# PWR-Switch.net
KiCad netlist of a schematic drawn in Altium Designer
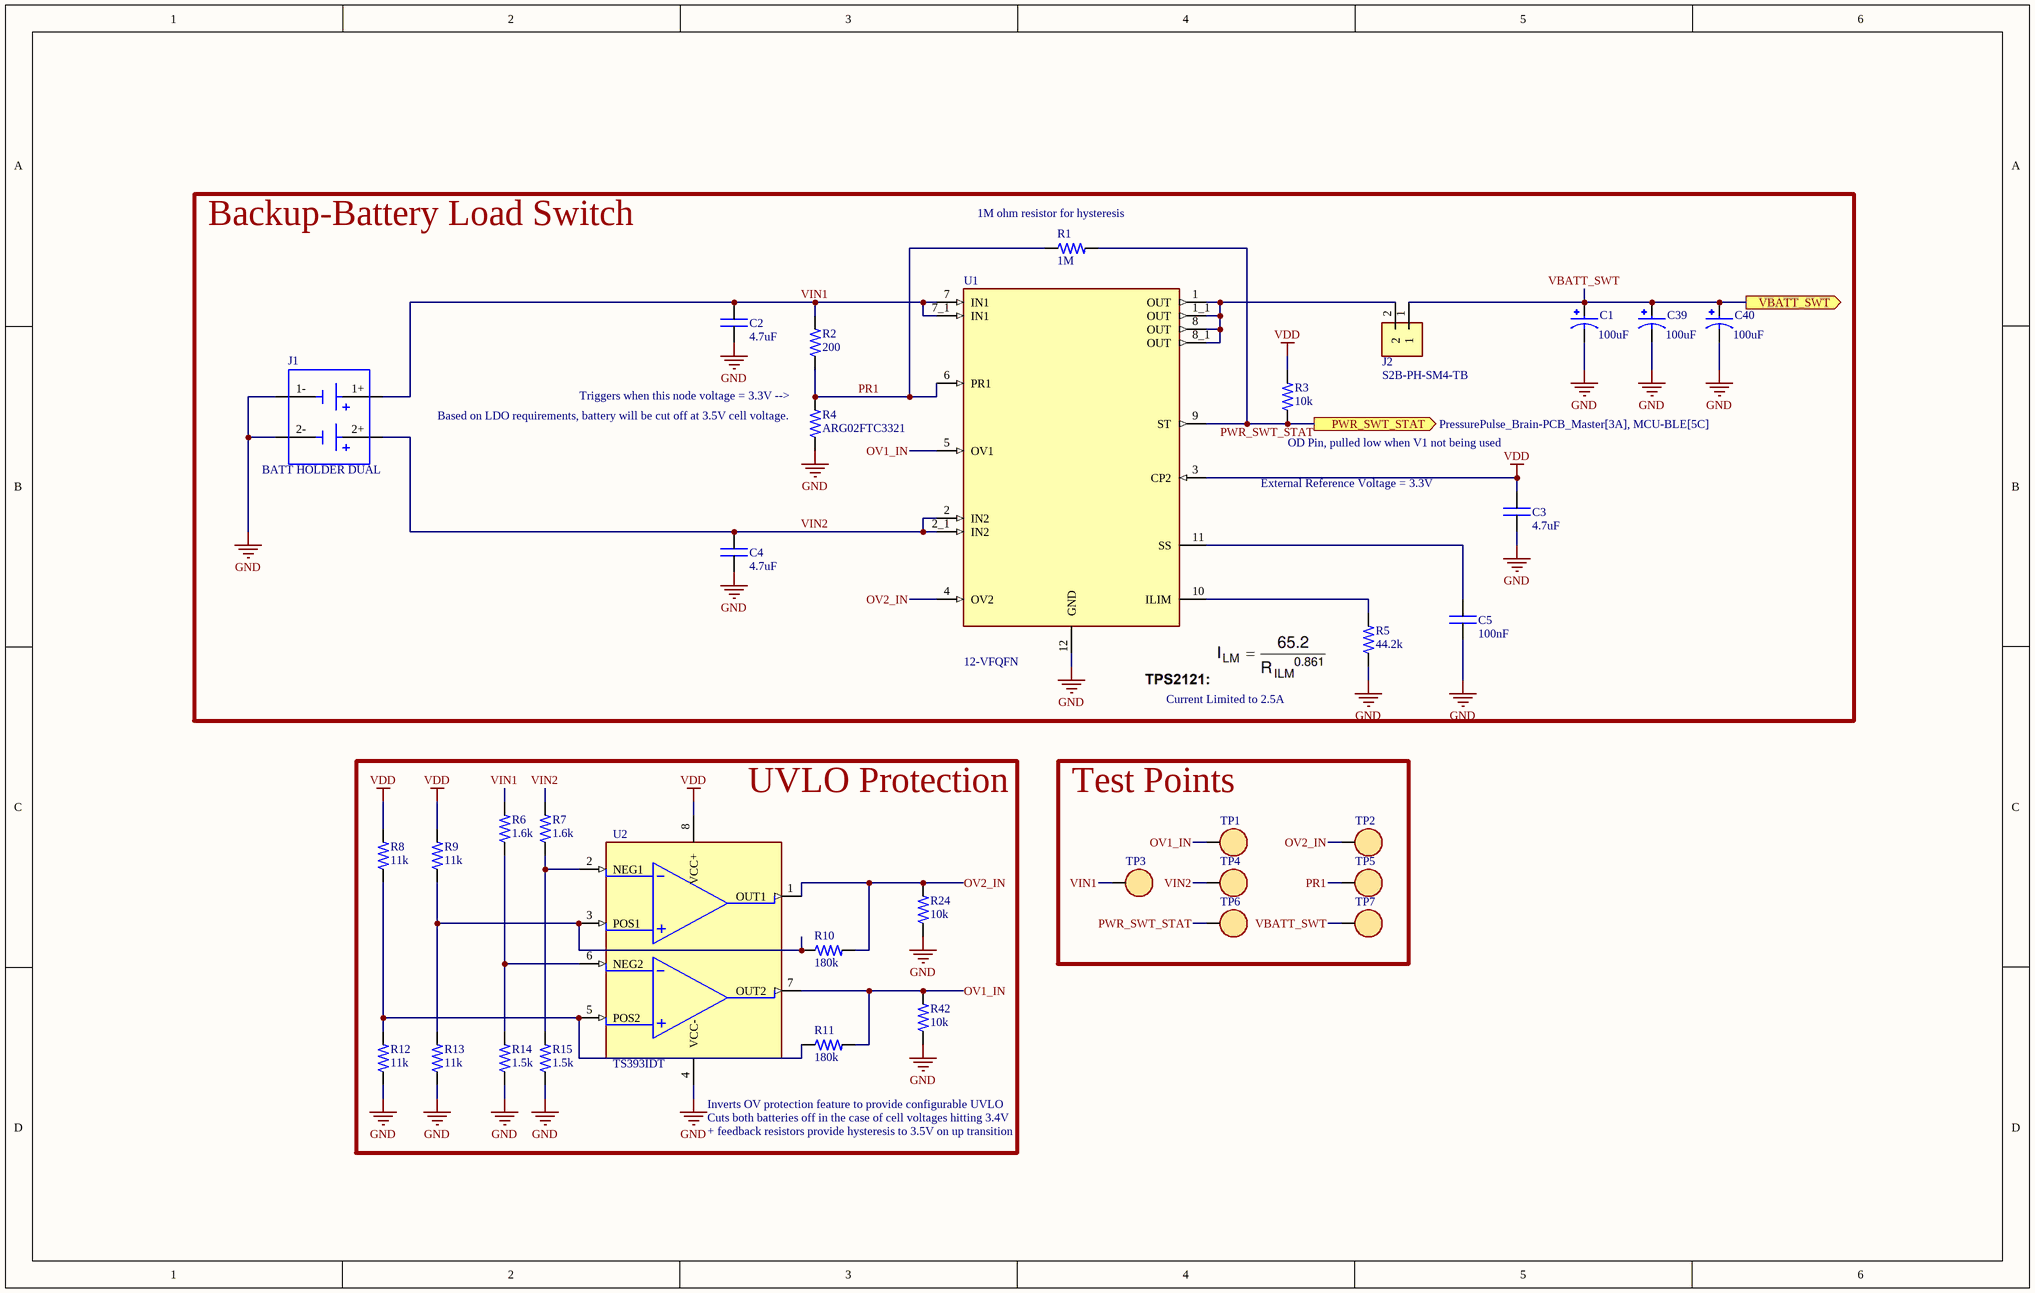
[diagram p0: PWR-Switch.SchDoc]

(export (version "E")
  (design (tool "Eeschema 10.0.6"))
  (components
    (comp (ref "C1")
      (value "100uF")
      (footprint "PressurePulse:CAP_POL_SMD")
      (fields (field (name "MFR") "PANASONIC") (field (name "Comment") "CAP POLARIZED"))
      (libsource (lib "PressurePulse") (part "CAP POLARIZED"))
    )
    (comp (ref "C2")
      (value "4.7uF")
      (footprint "PressurePulse:0402C")
      (description "Capacitor")
      (fields (field (name "Comment") "CAP"))
      (libsource (lib "PressurePulse") (part "CAP"))
    )
    (comp (ref "C3")
      (value "4.7uF")
      (footprint "PressurePulse:0402C")
      (description "Capacitor")
      (fields (field (name "Comment") "CAP"))
      (libsource (lib "PressurePulse") (part "CAP"))
    )
    (comp (ref "C4")
      (value "4.7uF")
      (footprint "PressurePulse:0402C")
      (description "Capacitor")
      (fields (field (name "Comment") "CAP"))
      (libsource (lib "PressurePulse") (part "CAP"))
    )
    (comp (ref "C5")
      (value "100nF")
      (footprint "PressurePulse:0402C")
      (description "Capaicitor")
      (fields (field (name "Comment") "CAP"))
      (libsource (lib "PressurePulse") (part "CAP"))
    )
    (comp (ref "C39")
      (value "100uF")
      (footprint "PressurePulse:CAP_POL_SMD")
      (fields (field (name "MFR") "PANASONIC") (field (name "Comment") "CAP POLARIZED"))
      (libsource (lib "PressurePulse") (part "CAP POLARIZED"))
    )
    (comp (ref "C40")
      (value "100uF")
      (footprint "PressurePulse:CAP_POL_SMD")
      (fields (field (name "MFR") "PANASONIC") (field (name "Comment") "CAP POLARIZED"))
      (libsource (lib "PressurePulse") (part "CAP POLARIZED"))
    )
    (comp (ref "J1")
      (value "BATT HOLDER DUAL")
      (footprint "PressurePulse:18650_DUAL_PARALLEL")
      (description "Battery Holder (Open) 18650 2 Cell PC Pin")
      (fields (field (name "MFR") "MPD (Memory Protection Devices)"))
      (libsource (lib "PressurePulse") (part "BATT HOLDER DUAL"))
    )
    (comp (ref "J2")
      (value "S2B-PH-SM4-TB")
      (footprint "PressurePulse:JST_PH-2POS-SMT-RA")
      (description "Connector Header Surface Mount, Right Angle 2 position 0.079 (2.00mm)")
      (fields (field (name "MFR") "JST Sales"))
      (libsource (lib "PressurePulse") (part "JST CONN 2POS PH"))
    )
    (comp (ref "R1")
      (value "1M")
      (footprint "PressurePulse:0402R")
      (description "Resistor")
      (fields (field (name "Comment") "RES"))
      (libsource (lib "PressurePulse") (part "RES"))
    )
    (comp (ref "R2")
      (value "200")
      (footprint "PressurePulse:0402R")
      (description "Resistor")
      (fields (field (name "TOLERANCE") "0.5%") (field (name "Comment") "RES"))
      (libsource (lib "PressurePulse") (part "RES"))
    )
    (comp (ref "R3")
      (value "10k")
      (footprint "PressurePulse:0402R")
      (description "Resistor")
      (fields (field (name "Comment") "RES"))
      (libsource (lib "PressurePulse") (part "RES"))
    )
    (comp (ref "R4")
      (value "ARG02FTC3321")
      (footprint "PressurePulse:0402R")
      (description "Resistor")
      (fields (field (name "TOLERANCE") "1%") (field (name "Comment") "RES"))
      (libsource (lib "PressurePulse") (part "RES"))
    )
    (comp (ref "R5")
      (value "44.2k")
      (footprint "PressurePulse:0402R")
      (description "Resistor")
      (fields (field (name "TOLERANCE") "1%") (field (name "Comment") "RES"))
      (libsource (lib "PressurePulse") (part "RES"))
    )
    (comp (ref "R6")
      (value "1.6k")
      (footprint "PressurePulse:0603-RES")
      (description "Resistor")
      (fields (field (name "TOLERANCE") "0.5%") (field (name "Comment") "RES"))
      (libsource (lib "PressurePulse") (part "RES"))
    )
    (comp (ref "R7")
      (value "1.6k")
      (footprint "PressurePulse:0603-RES")
      (description "Resistor")
      (fields (field (name "TOLERANCE") "0.5%") (field (name "Comment") "RES"))
      (libsource (lib "PressurePulse") (part "RES"))
    )
    (comp (ref "R8")
      (value "11k")
      (footprint "PressurePulse:0402R")
      (description "Resistor")
      (fields (field (name "TOLERANCE") "0.5%") (field (name "Comment") "RES"))
      (libsource (lib "PressurePulse") (part "RES"))
    )
    (comp (ref "R9")
      (value "11k")
      (footprint "PressurePulse:0402R")
      (description "Resistor")
      (fields (field (name "TOLERANCE") "0.5%") (field (name "Comment") "RES"))
      (libsource (lib "PressurePulse") (part "RES"))
    )
    (comp (ref "R10")
      (value "180k")
      (footprint "PressurePulse:0402R")
      (description "Resistor")
      (fields (field (name "Comment") "RES"))
      (libsource (lib "PressurePulse") (part "RES"))
    )
    (comp (ref "R11")
      (value "180k")
      (footprint "PressurePulse:0402R")
      (description "Resistor")
      (fields (field (name "Comment") "RES"))
      (libsource (lib "PressurePulse") (part "RES"))
    )
    (comp (ref "R12")
      (value "11k")
      (footprint "PressurePulse:0402R")
      (description "Resistor")
      (fields (field (name "TOLERANCE") "0.5%") (field (name "Comment") "RES"))
      (libsource (lib "PressurePulse") (part "RES"))
    )
    (comp (ref "R13")
      (value "11k")
      (footprint "PressurePulse:0402R")
      (description "Resistor")
      (fields (field (name "TOLERANCE") "0.5%") (field (name "Comment") "RES"))
      (libsource (lib "PressurePulse") (part "RES"))
    )
    (comp (ref "R14")
      (value "1.5k")
      (footprint "PressurePulse:0603-RES")
      (description "Resistor")
      (fields (field (name "TOLERANCE") "0.5%") (field (name "Comment") "RES"))
      (libsource (lib "PressurePulse") (part "RES"))
    )
    (comp (ref "R15")
      (value "1.5k")
      (footprint "PressurePulse:0603-RES")
      (description "Resistor")
      (fields (field (name "TOLERANCE") "0.5%") (field (name "Comment") "RES"))
      (libsource (lib "PressurePulse") (part "RES"))
    )
    (comp (ref "R24")
      (value "10k")
      (footprint "PressurePulse:0402R")
      (description "Resistor")
      (fields (field (name "Comment") "RES"))
      (libsource (lib "PressurePulse") (part "RES"))
    )
    (comp (ref "R42")
      (value "10k")
      (footprint "PressurePulse:0402R")
      (description "Resistor")
      (fields (field (name "Comment") "RES"))
      (libsource (lib "PressurePulse") (part "RES"))
    )
    (comp (ref "TP1")
      (value "RH-5019")
      (footprint "PressurePulse:TP - RH-5019")
      (fields (field (name "MFR") "ronghe"))
      (libsource (lib "PressurePulse") (part "TEST POINT"))
    )
    (comp (ref "TP2")
      (value "RH-5019")
      (footprint "PressurePulse:TP - RH-5019")
      (fields (field (name "MFR") "ronghe"))
      (libsource (lib "PressurePulse") (part "TEST POINT"))
    )
    (comp (ref "TP3")
      (value "RH-5019")
      (footprint "PressurePulse:TP - RH-5019")
      (fields (field (name "MFR") "ronghe"))
      (libsource (lib "PressurePulse") (part "TEST POINT"))
    )
    (comp (ref "TP4")
      (value "RH-5019")
      (footprint "PressurePulse:TP - RH-5019")
      (fields (field (name "MFR") "ronghe"))
      (libsource (lib "PressurePulse") (part "TEST POINT"))
    )
    (comp (ref "TP5")
      (value "RH-5019")
      (footprint "PressurePulse:TP - RH-5019")
      (fields (field (name "MFR") "ronghe"))
      (libsource (lib "PressurePulse") (part "TEST POINT"))
    )
    (comp (ref "TP6")
      (value "RH-5019")
      (footprint "PressurePulse:TP - RH-5019")
      (fields (field (name "MFR") "ronghe"))
      (libsource (lib "PressurePulse") (part "TEST POINT"))
    )
    (comp (ref "TP7")
      (value "RH-5019")
      (footprint "PressurePulse:TP - RH-5019")
      (fields (field (name "MFR") "ronghe"))
      (libsource (lib "PressurePulse") (part "TEST POINT"))
    )
    (comp (ref "U1")
      (value "12-VFQFN")
      (footprint "PressurePulse:12-VFQFN")
      (description "2.7-V to 22-V, 56-ma, 4.5-A, power mux with seamless switchover")
      (fields (field (name "MFR") "Texas Instruments"))
      (libsource (lib "PressurePulse") (part "TPS2121RUXR"))
    )
    (comp (ref "U2")
      (value "TS393IDT")
      (footprint "PressurePulse:SOIC-8")
      (description "Micropower dual CMOS voltage comparators")
      (fields (field (name "MFR") "STMicroelectronics"))
      (libsource (lib "PressurePulse") (part "DUAL COMPARATOR"))
    )
  )
  (nets
    (net (code "1") (name "/OV1_IN") (class "Default")
      (node (ref "R11") (pin "2") (pinfunction "2_2") (pintype "passive"))
      (node (ref "R42") (pin "2") (pinfunction "2_2") (pintype "passive"))
      (node (ref "TP1") (pin "1") (pinfunction "1_1") (pintype "passive"))
      (node (ref "U1") (pin "5") (pinfunction "OV1_5") (pintype "input"))
      (node (ref "U2") (pin "7") (pinfunction "OUT2_7") (pintype "output"))
    )
    (net (code "2") (name "/OV2_IN") (class "Default")
      (node (ref "R10") (pin "2") (pinfunction "2_2") (pintype "passive"))
      (node (ref "R24") (pin "2") (pinfunction "2_2") (pintype "passive"))
      (node (ref "TP2") (pin "1") (pinfunction "1_1") (pintype "passive"))
      (node (ref "U1") (pin "4") (pinfunction "OV2_4") (pintype "input"))
      (node (ref "U2") (pin "1") (pinfunction "OUT1_1") (pintype "output"))
    )
    (net (code "3") (name "/PR1") (class "Default")
      (node (ref "R1") (pin "1") (pinfunction "1_1") (pintype "passive"))
      (node (ref "R2") (pin "1") (pinfunction "1_1") (pintype "passive"))
      (node (ref "R4") (pin "2") (pinfunction "2_2") (pintype "passive"))
      (node (ref "TP5") (pin "1") (pinfunction "1_1") (pintype "passive"))
      (node (ref "U1") (pin "6") (pinfunction "PR1_6") (pintype "input"))
    )
    (net (code "4") (name "/PWR_SWT_STAT") (class "Default")
      (node (ref "R1") (pin "2") (pinfunction "2_2") (pintype "passive"))
      (node (ref "R3") (pin "1") (pinfunction "1_1") (pintype "passive"))
      (node (ref "TP6") (pin "1") (pinfunction "1_1") (pintype "passive"))
      (node (ref "U1") (pin "9") (pinfunction "ST_9") (pintype "output"))
    )
    (net (code "5") (name "/VBATT_SWT") (class "Default")
      (node (ref "C1") (pin "1") (pinfunction "1_1") (pintype "passive"))
      (node (ref "C39") (pin "1") (pinfunction "1_1") (pintype "passive"))
      (node (ref "C40") (pin "1") (pinfunction "1_1") (pintype "passive"))
      (node (ref "J2") (pin "1") (pinfunction "1_1") (pintype "passive"))
      (node (ref "TP7") (pin "1") (pinfunction "1_1") (pintype "passive"))
    )
    (net (code "6") (name "/VIN1") (class "Default")
      (node (ref "C2") (pin "2") (pinfunction "2_2") (pintype "passive"))
      (node (ref "J1") (pin "1+") (pinfunction "1+_1+") (pintype "passive"))
      (node (ref "R2") (pin "2") (pinfunction "2_2") (pintype "passive"))
      (node (ref "R6") (pin "2") (pinfunction "2_2") (pintype "passive"))
      (node (ref "TP3") (pin "1") (pinfunction "1_1") (pintype "passive"))
      (node (ref "U1") (pin "7") (pinfunction "IN1_7") (pintype "input"))
      (node (ref "U1") (pin "7_1") (pinfunction "IN1_7_1") (pintype "input"))
    )
    (net (code "7") (name "/VIN2") (class "Default")
      (node (ref "C4") (pin "2") (pinfunction "2_2") (pintype "passive"))
      (node (ref "J1") (pin "2+") (pinfunction "2+_2+") (pintype "passive"))
      (node (ref "R7") (pin "2") (pinfunction "2_2") (pintype "passive"))
      (node (ref "TP4") (pin "1") (pinfunction "1_1") (pintype "passive"))
      (node (ref "U1") (pin "2") (pinfunction "IN2_2") (pintype "input"))
      (node (ref "U1") (pin "2_1") (pinfunction "IN2_2_1") (pintype "input"))
    )
    (net (code "8") (name "GND") (class "Default")
      (node (ref "C1") (pin "2") (pinfunction "2_2") (pintype "passive"))
      (node (ref "C2") (pin "1") (pinfunction "1_1") (pintype "passive"))
      (node (ref "C3") (pin "1") (pinfunction "1_1") (pintype "passive"))
      (node (ref "C39") (pin "2") (pinfunction "2_2") (pintype "passive"))
      (node (ref "C4") (pin "1") (pinfunction "1_1") (pintype "passive"))
      (node (ref "C40") (pin "2") (pinfunction "2_2") (pintype "passive"))
      (node (ref "C5") (pin "1") (pinfunction "1_1") (pintype "passive"))
      (node (ref "J1") (pin "1-") (pinfunction "1-_1-") (pintype "passive"))
      (node (ref "J1") (pin "2-") (pinfunction "2-_2-") (pintype "passive"))
      (node (ref "R12") (pin "1") (pinfunction "1_1") (pintype "passive"))
      (node (ref "R13") (pin "1") (pinfunction "1_1") (pintype "passive"))
      (node (ref "R14") (pin "1") (pinfunction "1_1") (pintype "passive"))
      (node (ref "R15") (pin "1") (pinfunction "1_1") (pintype "passive"))
      (node (ref "R24") (pin "1") (pinfunction "1_1") (pintype "passive"))
      (node (ref "R4") (pin "1") (pinfunction "1_1") (pintype "passive"))
      (node (ref "R42") (pin "1") (pinfunction "1_1") (pintype "passive"))
      (node (ref "R5") (pin "1") (pinfunction "1_1") (pintype "passive"))
      (node (ref "U1") (pin "12") (pinfunction "GND_12") (pintype "power_in"))
      (node (ref "U2") (pin "4") (pinfunction "VCC-_4") (pintype "power_in"))
    )
    (net (code "9") (name "Net-(J2-Pad2)") (class "Default")
      (node (ref "J2") (pin "2") (pinfunction "2_2") (pintype "passive"))
      (node (ref "U1") (pin "1") (pinfunction "OUT_1") (pintype "output"))
      (node (ref "U1") (pin "1_1") (pinfunction "OUT_1_1") (pintype "output"))
      (node (ref "U1") (pin "8") (pinfunction "OUT_8") (pintype "output"))
      (node (ref "U1") (pin "8_1") (pinfunction "OUT_8_1") (pintype "output"))
    )
    (net (code "10") (name "Net-(U1-ILIM)") (class "Default")
      (node (ref "R5") (pin "2") (pinfunction "2_2") (pintype "passive"))
      (node (ref "U1") (pin "10") (pinfunction "ILIM_10") (pintype "passive"))
    )
    (net (code "11") (name "Net-(U1-SS)") (class "Default")
      (node (ref "C5") (pin "2") (pinfunction "2_2") (pintype "passive"))
      (node (ref "U1") (pin "11") (pinfunction "SS_11") (pintype "passive"))
    )
    (net (code "12") (name "Net-(U2-NEG1)") (class "Default")
      (node (ref "R15") (pin "2") (pinfunction "2_2") (pintype "passive"))
      (node (ref "R7") (pin "1") (pinfunction "1_1") (pintype "passive"))
      (node (ref "U2") (pin "2") (pinfunction "NEG1_2") (pintype "input"))
    )
    (net (code "13") (name "Net-(U2-NEG2)") (class "Default")
      (node (ref "R14") (pin "2") (pinfunction "2_2") (pintype "passive"))
      (node (ref "R6") (pin "1") (pinfunction "1_1") (pintype "passive"))
      (node (ref "U2") (pin "6") (pinfunction "NEG2_6") (pintype "input"))
    )
    (net (code "14") (name "Net-(U2-POS1)") (class "Default")
      (node (ref "R10") (pin "1") (pinfunction "1_1") (pintype "passive"))
      (node (ref "R13") (pin "2") (pinfunction "2_2") (pintype "passive"))
      (node (ref "R9") (pin "1") (pinfunction "1_1") (pintype "passive"))
      (node (ref "U2") (pin "3") (pinfunction "POS1_3") (pintype "input"))
    )
    (net (code "15") (name "Net-(U2-POS2)") (class "Default")
      (node (ref "R11") (pin "1") (pinfunction "1_1") (pintype "passive"))
      (node (ref "R12") (pin "2") (pinfunction "2_2") (pintype "passive"))
      (node (ref "R8") (pin "1") (pinfunction "1_1") (pintype "passive"))
      (node (ref "U2") (pin "5") (pinfunction "POS2_5") (pintype "input"))
    )
    (net (code "16") (name "VDD") (class "Default")
      (node (ref "C3") (pin "2") (pinfunction "2_2") (pintype "passive"))
      (node (ref "R3") (pin "2") (pinfunction "2_2") (pintype "passive"))
      (node (ref "R8") (pin "2") (pinfunction "2_2") (pintype "passive"))
      (node (ref "R9") (pin "2") (pinfunction "2_2") (pintype "passive"))
      (node (ref "U1") (pin "3") (pinfunction "CP2_3") (pintype "input"))
      (node (ref "U2") (pin "8") (pinfunction "VCC+_8") (pintype "power_in"))
    )
  )
)
